# Interfaces.net
KiCad netlist of a schematic drawn in Altium Designer
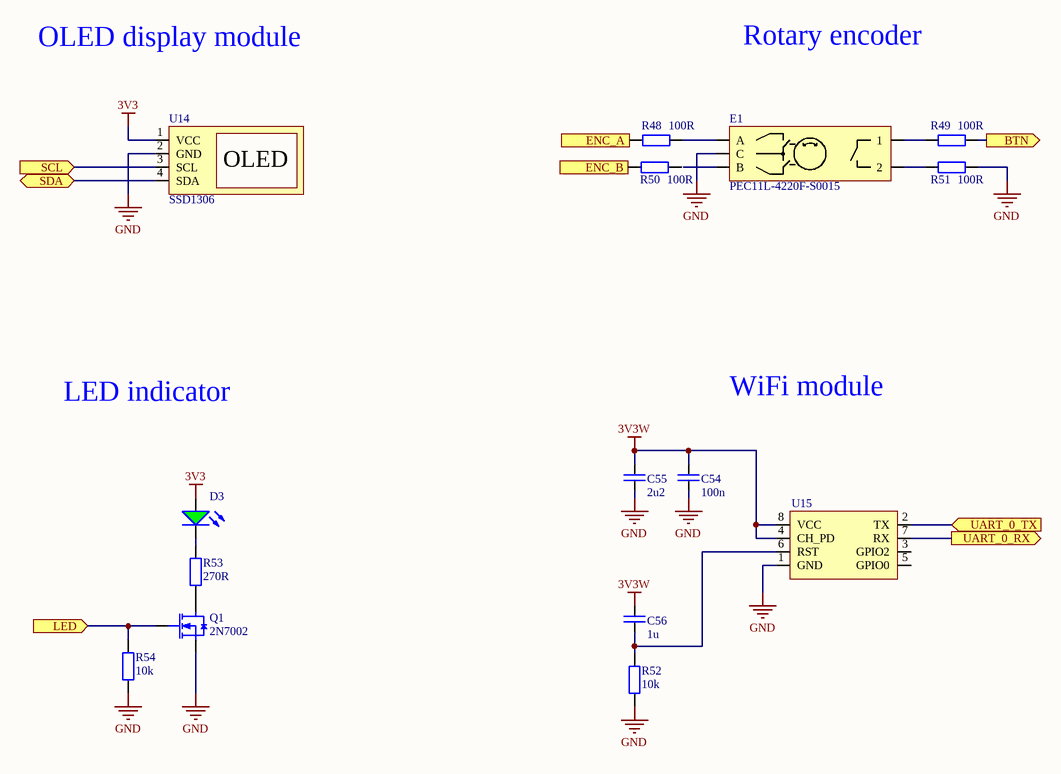
[diagram p0: Interfaces.SchDoc]

(export (version "E")
  (design (tool "Eeschema 10.0.6"))
  (components
    (comp (ref "C54")
      (value "100n")
      (footprint "C_0603")
      (description "Generic capacitor")
      (libsource (lib "DAQ_REV_B") (part "Capacitor"))
    )
    (comp (ref "C55")
      (value "2u2")
      (footprint "C_0603")
      (description "Generic capacitor")
      (libsource (lib "DAQ_REV_B") (part "Capacitor"))
    )
    (comp (ref "C56")
      (value "1u")
      (footprint "C_0603")
      (description "Generic capacitor")
      (libsource (lib "DAQ_REV_B") (part "Capacitor"))
    )
    (comp (ref "D3")
      (value "LED Green")
      (footprint "LED_0603")
      (description "Generic LED Green")
      (libsource (lib "DAQ_REV_B") (part "LED Green"))
    )
    (comp (ref "E1")
      (value "PEC11L-4220F-S0015")
      (footprint "PEC11L")
      (description "Low Profile Encoder 15 PPR 2 Bit Quadrature 5VDC at 10 mA IP40 PCB Mount")
      (fields (field (name "MANUFACTURER") "BOURNS"))
      (libsource (lib "DAQ") (part "PEC11L-4220F-S0015"))
    )
    (comp (ref "Q1")
      (value "2N7002")
      (footprint "SOT23-3")
      (description "60V 0.3A N-channel MOSFET")
      (fields (field (name "PART NUMBER") "XMN0002") (field (name "MANUFACTURER") "NXP"))
      (libsource (lib "DAQ_REV_B") (part "2N7002"))
    )
    (comp (ref "R48")
      (value "100R")
      (footprint "R_0603")
      (description "Generic resistor")
      (libsource (lib "DAQ_REV_B") (part "Resistor"))
    )
    (comp (ref "R49")
      (value "100R")
      (footprint "R_0603")
      (description "Generic resistor")
      (libsource (lib "DAQ_REV_B") (part "Resistor"))
    )
    (comp (ref "R50")
      (value "100R")
      (footprint "R_0603")
      (description "Generic resistor")
      (libsource (lib "DAQ_REV_B") (part "Resistor"))
    )
    (comp (ref "R51")
      (value "100R")
      (footprint "R_0603")
      (description "Generic resistor")
      (libsource (lib "DAQ_REV_B") (part "Resistor"))
    )
    (comp (ref "R52")
      (value "10k")
      (footprint "R_0603")
      (description "Generic resistor")
      (libsource (lib "DAQ_REV_B") (part "Resistor"))
    )
    (comp (ref "R53")
      (value "270R")
      (footprint "R_0603")
      (description "Generic resistor")
      (libsource (lib "DAQ_REV_B") (part "Resistor"))
    )
    (comp (ref "R54")
      (value "10k")
      (footprint "R_0603")
      (description "Generic resistor")
      (libsource (lib "DAQ_REV_B") (part "Resistor"))
    )
    (comp (ref "U14")
      (value "SSD1306")
      (footprint "OLED1")
      (description "Oled display module")
      (fields (field (name "PART NUMBER") "OLM0000"))
      (libsource (lib "DAQ_REV_B") (part "OLED_SSD1306"))
    )
    (comp (ref "U15")
      (value "ESP-01")
      (footprint "ESP-01")
      (description "WIFI module")
      (fields (field (name "PART NUMBER") "XWM0000"))
      (libsource (lib "DAQ_REV_B") (part "ESP-01"))
    )
  )
  (nets
    (net (code "1") (name "/BTN") (class "Default") (node (ref "R49") (pin "2") (pintype "passive")))
    (net (code "2") (name "/ENC_A") (class "Default") (node (ref "R48") (pin "1") (pintype "passive")))
    (net (code "3") (name "/ENC_B") (class "Default") (node (ref "R50") (pin "1") (pintype "passive")))
    (net (code "4") (name "/LED") (class "Default")
      (node (ref "Q1") (pin "1") (pinfunction "G_1") (pintype "passive"))
      (node (ref "R54") (pin "2") (pintype "passive"))
    )
    (net (code "5") (name "/SCL") (class "Default")
      (node (ref "U14") (pin "3") (pinfunction "SCL_3") (pintype "passive"))
    )
    (net (code "6") (name "/SDA") (class "Default")
      (node (ref "U14") (pin "4") (pinfunction "SDA_4") (pintype "passive"))
    )
    (net (code "7") (name "/UART_0_RX") (class "Default")
      (node (ref "U15") (pin "7") (pinfunction "RX_7") (pintype "passive"))
    )
    (net (code "8") (name "/UART_0_TX") (class "Default")
      (node (ref "U15") (pin "2") (pinfunction "TX_2") (pintype "passive"))
    )
    (net (code "9") (name "3V3") (class "Default")
      (node (ref "D3") (pin "2") (pinfunction "+_2") (pintype "passive"))
      (node (ref "U14") (pin "1") (pinfunction "VCC_1") (pintype "passive"))
    )
    (net (code "10") (name "3V3W") (class "Default")
      (node (ref "C54") (pin "2") (pinfunction "2_2") (pintype "passive"))
      (node (ref "C55") (pin "2") (pinfunction "2_2") (pintype "passive"))
      (node (ref "C56") (pin "2") (pinfunction "2_2") (pintype "passive"))
      (node (ref "U15") (pin "4") (pinfunction "CH_PD_4") (pintype "passive"))
      (node (ref "U15") (pin "8") (pinfunction "VCC_8") (pintype "passive"))
    )
    (net (code "11") (name "GND") (class "Default")
      (node (ref "C54") (pin "1") (pinfunction "1_1") (pintype "passive"))
      (node (ref "C55") (pin "1") (pinfunction "1_1") (pintype "passive"))
      (node (ref "E1") (pin "C") (pinfunction "C_C") (pintype "passive"))
      (node (ref "Q1") (pin "2") (pinfunction "S_2") (pintype "passive"))
      (node (ref "R51") (pin "2") (pintype "passive"))
      (node (ref "R52") (pin "1") (pintype "passive"))
      (node (ref "R54") (pin "1") (pintype "passive"))
      (node (ref "U14") (pin "2") (pinfunction "GND_2") (pintype "passive"))
      (node (ref "U15") (pin "1") (pinfunction "GND_1") (pintype "passive"))
    )
    (net (code "12") (name "Net-(D3--)") (class "Default")
      (node (ref "D3") (pin "1") (pinfunction "-_1") (pintype "passive"))
      (node (ref "R53") (pin "2") (pintype "passive"))
    )
    (net (code "13") (name "Net-(E1-Pad1)") (class "Default")
      (node (ref "E1") (pin "1") (pinfunction "1_1") (pintype "passive"))
      (node (ref "R49") (pin "1") (pintype "passive"))
    )
    (net (code "14") (name "Net-(E1-Pad2)") (class "Default")
      (node (ref "E1") (pin "2") (pinfunction "2_2") (pintype "passive"))
      (node (ref "R51") (pin "1") (pintype "passive"))
    )
    (net (code "15") (name "Net-(E1-PadA)") (class "Default")
      (node (ref "E1") (pin "A") (pinfunction "A_A") (pintype "passive"))
      (node (ref "R48") (pin "2") (pintype "passive"))
    )
    (net (code "16") (name "Net-(Q1-D)") (class "Default")
      (node (ref "Q1") (pin "3") (pinfunction "D_3") (pintype "passive"))
      (node (ref "R53") (pin "1") (pintype "passive"))
    )
    (net (code "17") (name "Net-(U15-RST)") (class "Default")
      (node (ref "C56") (pin "1") (pinfunction "1_1") (pintype "passive"))
      (node (ref "R52") (pin "2") (pintype "passive"))
      (node (ref "U15") (pin "6") (pinfunction "RST_6") (pintype "passive"))
    )
    (net (code "18") (name "unconnected-(E1-PadB)") (class "Default")
      (node (ref "E1") (pin "B") (pinfunction "B_B") (pintype "passive"))
    )
    (net (code "19") (name "unconnected-(R50-Pad2)") (class "Default")
      (node (ref "R50") (pin "2") (pintype "passive"))
    )
    (net (code "20") (name "unconnected-(U15-GPIO0-Pad5)") (class "Default")
      (node (ref "U15") (pin "5") (pinfunction "GPIO0_5") (pintype "passive"))
    )
    (net (code "21") (name "unconnected-(U15-GPIO2-Pad3)") (class "Default")
      (node (ref "U15") (pin "3") (pinfunction "GPIO2_3") (pintype "passive"))
    )
  )
)
